# sensor-ds2406P.net
KiCad netlist of a schematic drawn in EAGLE
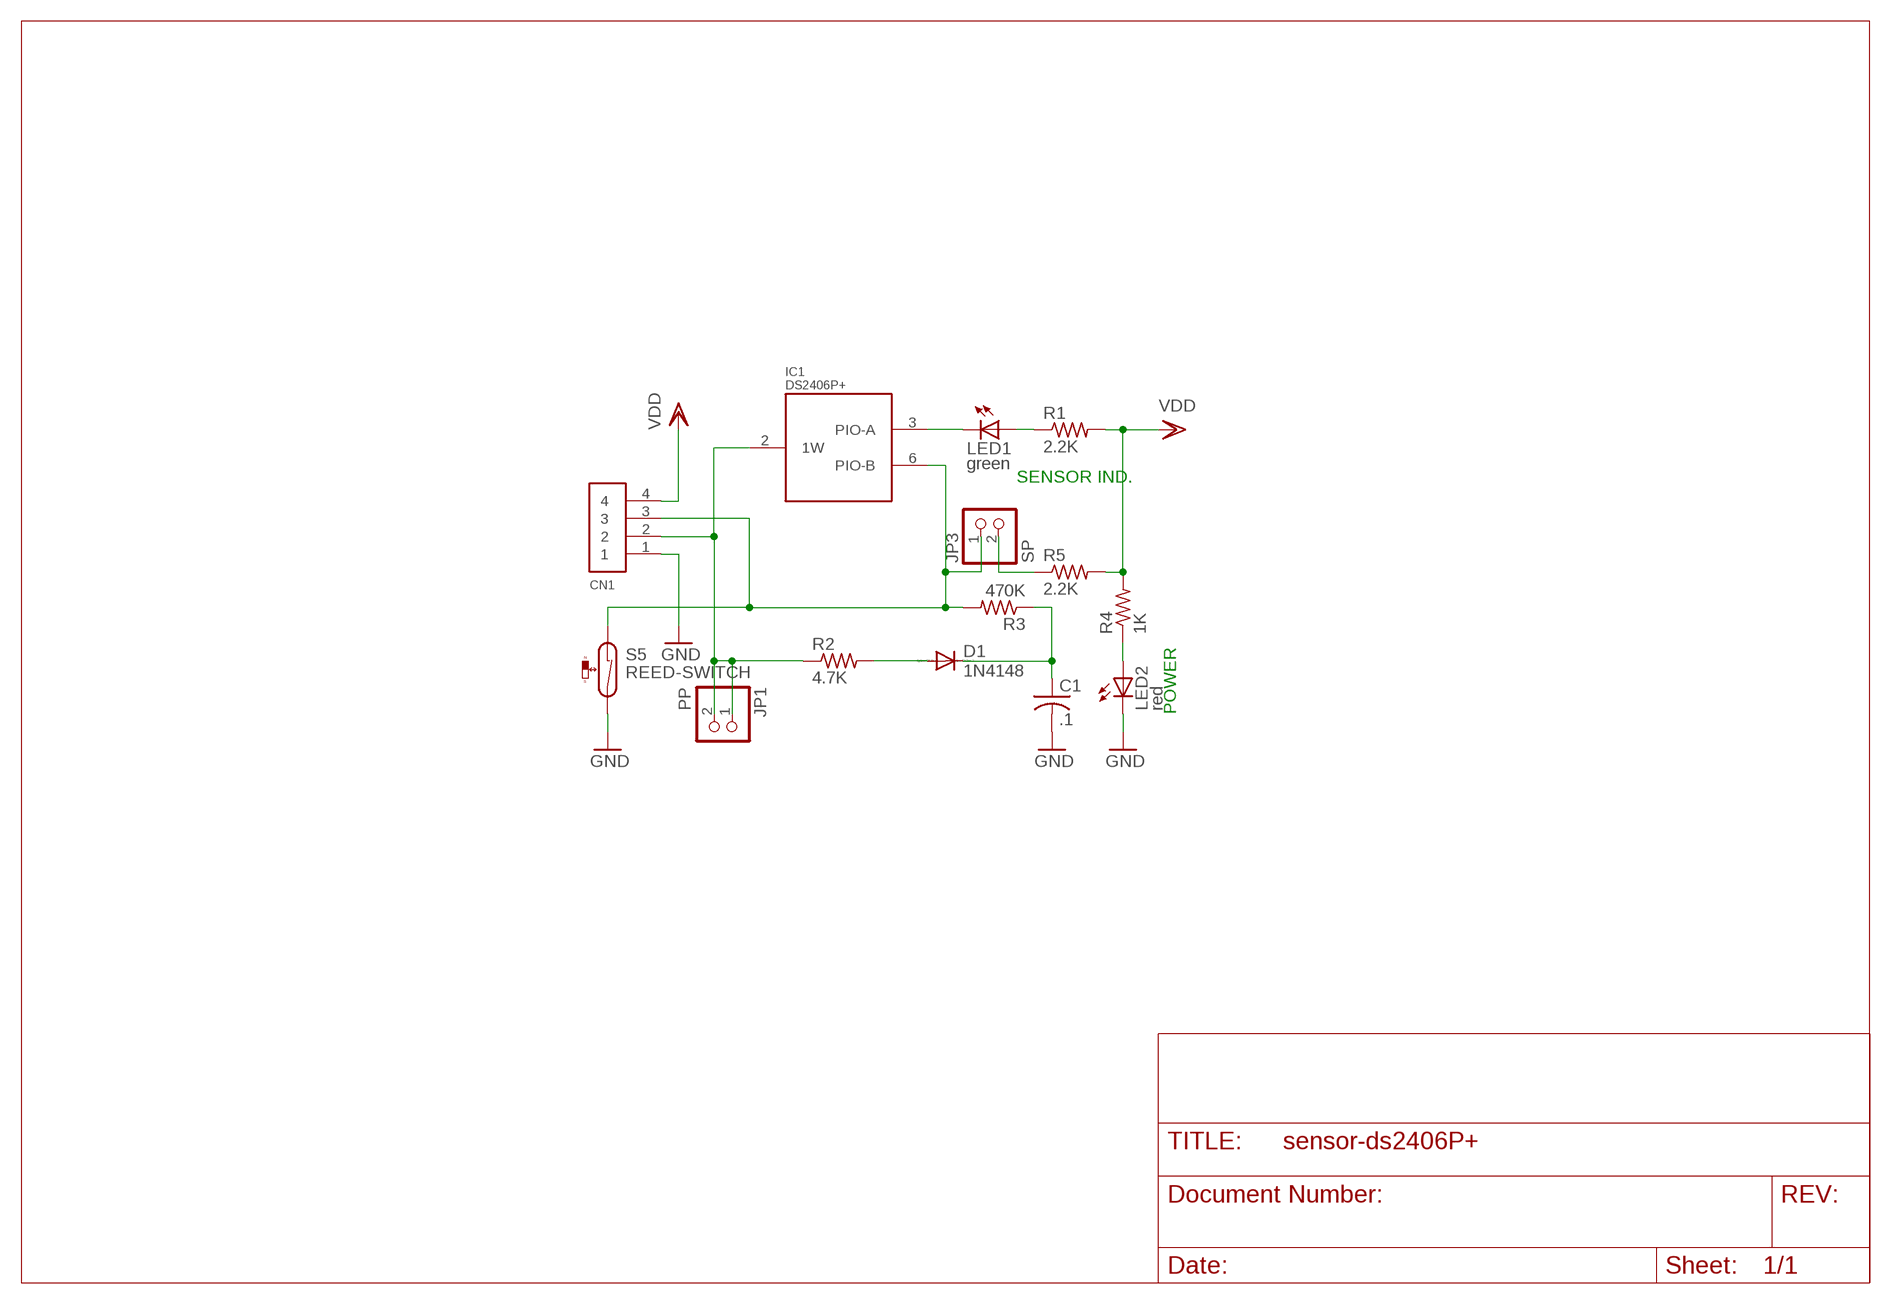
[diagram p0: schematic, sheet 1]

(export (version "E")
  (design (tool "Eeschema 10.0.6"))
  (components
    (comp (ref "C1")
      (value ".1")
      (footprint "eagle-import:C0805K")
      (libsource (lib "eagle-import") (part "C-USC0805K"))
    )
    (comp (ref "CN1")
      (value "1X4-BIG")
      (footprint "eagle-import:1X04-BIG")
      (libsource (lib "eagle-import") (part "1X4-BIG"))
    )
    (comp (ref "D1")
      (value "1N4148")
      (footprint "eagle-import:SOT23")
      (libsource (lib "eagle-import") (part "MMBF1N4148MMBD4148"))
    )
    (comp (ref "IC1")
      (value "DS2406P+")
      (footprint "eagle-import:SO06")
      (libsource (lib "eagle-import") (part "DS2406P+"))
    )
    (comp (ref "JP1")
      (value "PP")
      (footprint "eagle-import:1X02")
      (libsource (lib "eagle-import") (part "PINHD-1X2"))
    )
    (comp (ref "JP3")
      (value "SP")
      (footprint "eagle-import:1X02")
      (libsource (lib "eagle-import") (part "PINHD-1X2"))
    )
    (comp (ref "LED1")
      (value "green")
      (footprint "eagle-import:LED3MM")
      (libsource (lib "eagle-import") (part "LED3MM"))
    )
    (comp (ref "LED2")
      (value "red")
      (footprint "eagle-import:LED3MM")
      (libsource (lib "eagle-import") (part "LED3MM"))
    )
    (comp (ref "R1")
      (value "2.2K")
      (footprint "eagle-import:R0805")
      (libsource (lib "eagle-import") (part "R-US_R0805"))
    )
    (comp (ref "R2")
      (value "4.7K")
      (footprint "eagle-import:R0805")
      (libsource (lib "eagle-import") (part "R-US_R0805"))
    )
    (comp (ref "R3")
      (value "470K")
      (footprint "eagle-import:R0805")
      (libsource (lib "eagle-import") (part "resistor_R-US_R0805"))
    )
    (comp (ref "R4")
      (value "1K")
      (footprint "eagle-import:R0805")
      (libsource (lib "eagle-import") (part "resistor_R-US_R0805"))
    )
    (comp (ref "R5")
      (value "2.2K")
      (footprint "eagle-import:R0805")
      (libsource (lib "eagle-import") (part "resistor_R-US_R0805"))
    )
    (comp (ref "S5")
      (value "REED-SWITCH")
      (footprint "eagle-import:MK15")
      (fields (field (name "MF") "MEDER") (field (name "MPN") "MK15-C-2"))
      (libsource (lib "eagle-import") (part "REED-SWITCH-MK15-C2"))
    )
  )
  (nets
    (net (code "1") (name "GND") (class "Default")
      (node (ref "C1") (pin "2") (pinfunction "2_2") (pintype "passive"))
      (node (ref "CN1") (pin "1") (pinfunction "1_1") (pintype "bidirectional"))
      (node (ref "LED2") (pin "K") (pinfunction "C_K") (pintype "passive"))
      (node (ref "S5") (pin "2") (pinfunction "2_2") (pintype "passive"))
    )
    (net (code "2") (name "Net-(D1-A)") (class "Default")
      (node (ref "D1") (pin "1") (pinfunction "A_1") (pintype "passive"))
      (node (ref "R2") (pin "2") (pinfunction "2_2") (pintype "passive"))
    )
    (net (code "3") (name "Net-(D1-C)") (class "Default")
      (node (ref "C1") (pin "1") (pinfunction "1_1") (pintype "passive"))
      (node (ref "D1") (pin "3") (pinfunction "C_3") (pintype "passive"))
      (node (ref "R3") (pin "1") (pinfunction "1_1") (pintype "passive"))
    )
    (net (code "4") (name "Net-(IC1A-1W)") (class "Default")
      (node (ref "CN1") (pin "2") (pinfunction "2_2") (pintype "bidirectional"))
      (node (ref "IC1") (pin "2") (pinfunction "1W_2") (pintype "bidirectional"))
      (node (ref "JP1") (pin "1") (pinfunction "1_1") (pintype "passive"))
      (node (ref "JP1") (pin "2") (pinfunction "2_2") (pintype "passive"))
      (node (ref "R2") (pin "1") (pinfunction "1_1") (pintype "passive"))
    )
    (net (code "5") (name "Net-(IC1A-PIO-A)") (class "Default")
      (node (ref "IC1") (pin "3") (pinfunction "PIO-A_3") (pintype "output"))
      (node (ref "LED1") (pin "K") (pinfunction "C_K") (pintype "passive"))
    )
    (net (code "6") (name "Net-(IC1A-PIO-B)") (class "Default")
      (node (ref "CN1") (pin "3") (pinfunction "3_3") (pintype "bidirectional"))
      (node (ref "IC1") (pin "6") (pinfunction "PIO-B_6") (pintype "open_collector"))
      (node (ref "JP3") (pin "1") (pinfunction "1_1") (pintype "passive"))
      (node (ref "R3") (pin "2") (pinfunction "2_2") (pintype "passive"))
      (node (ref "S5") (pin "1") (pinfunction "1_1") (pintype "passive"))
    )
    (net (code "7") (name "Net-(JP3-Pad2)") (class "Default")
      (node (ref "JP3") (pin "2") (pinfunction "2_2") (pintype "passive"))
      (node (ref "R5") (pin "1") (pinfunction "1_1") (pintype "passive"))
    )
    (net (code "8") (name "Net-(LED1-PadA)") (class "Default")
      (node (ref "LED1") (pin "A") (pinfunction "A_A") (pintype "passive"))
      (node (ref "R1") (pin "1") (pinfunction "1_1") (pintype "passive"))
    )
    (net (code "9") (name "Net-(LED2-PadA)") (class "Default")
      (node (ref "LED2") (pin "A") (pinfunction "A_A") (pintype "passive"))
      (node (ref "R4") (pin "1") (pinfunction "1_1") (pintype "passive"))
    )
    (net (code "10") (name "VDD") (class "Default")
      (node (ref "CN1") (pin "4") (pinfunction "4_4") (pintype "bidirectional"))
      (node (ref "R1") (pin "2") (pinfunction "2_2") (pintype "passive"))
      (node (ref "R4") (pin "2") (pinfunction "2_2") (pintype "passive"))
      (node (ref "R5") (pin "2") (pinfunction "2_2") (pintype "passive"))
    )
  )
)
